# wiring_bord.net
KiCad netlist of a schematic drawn in EAGLE
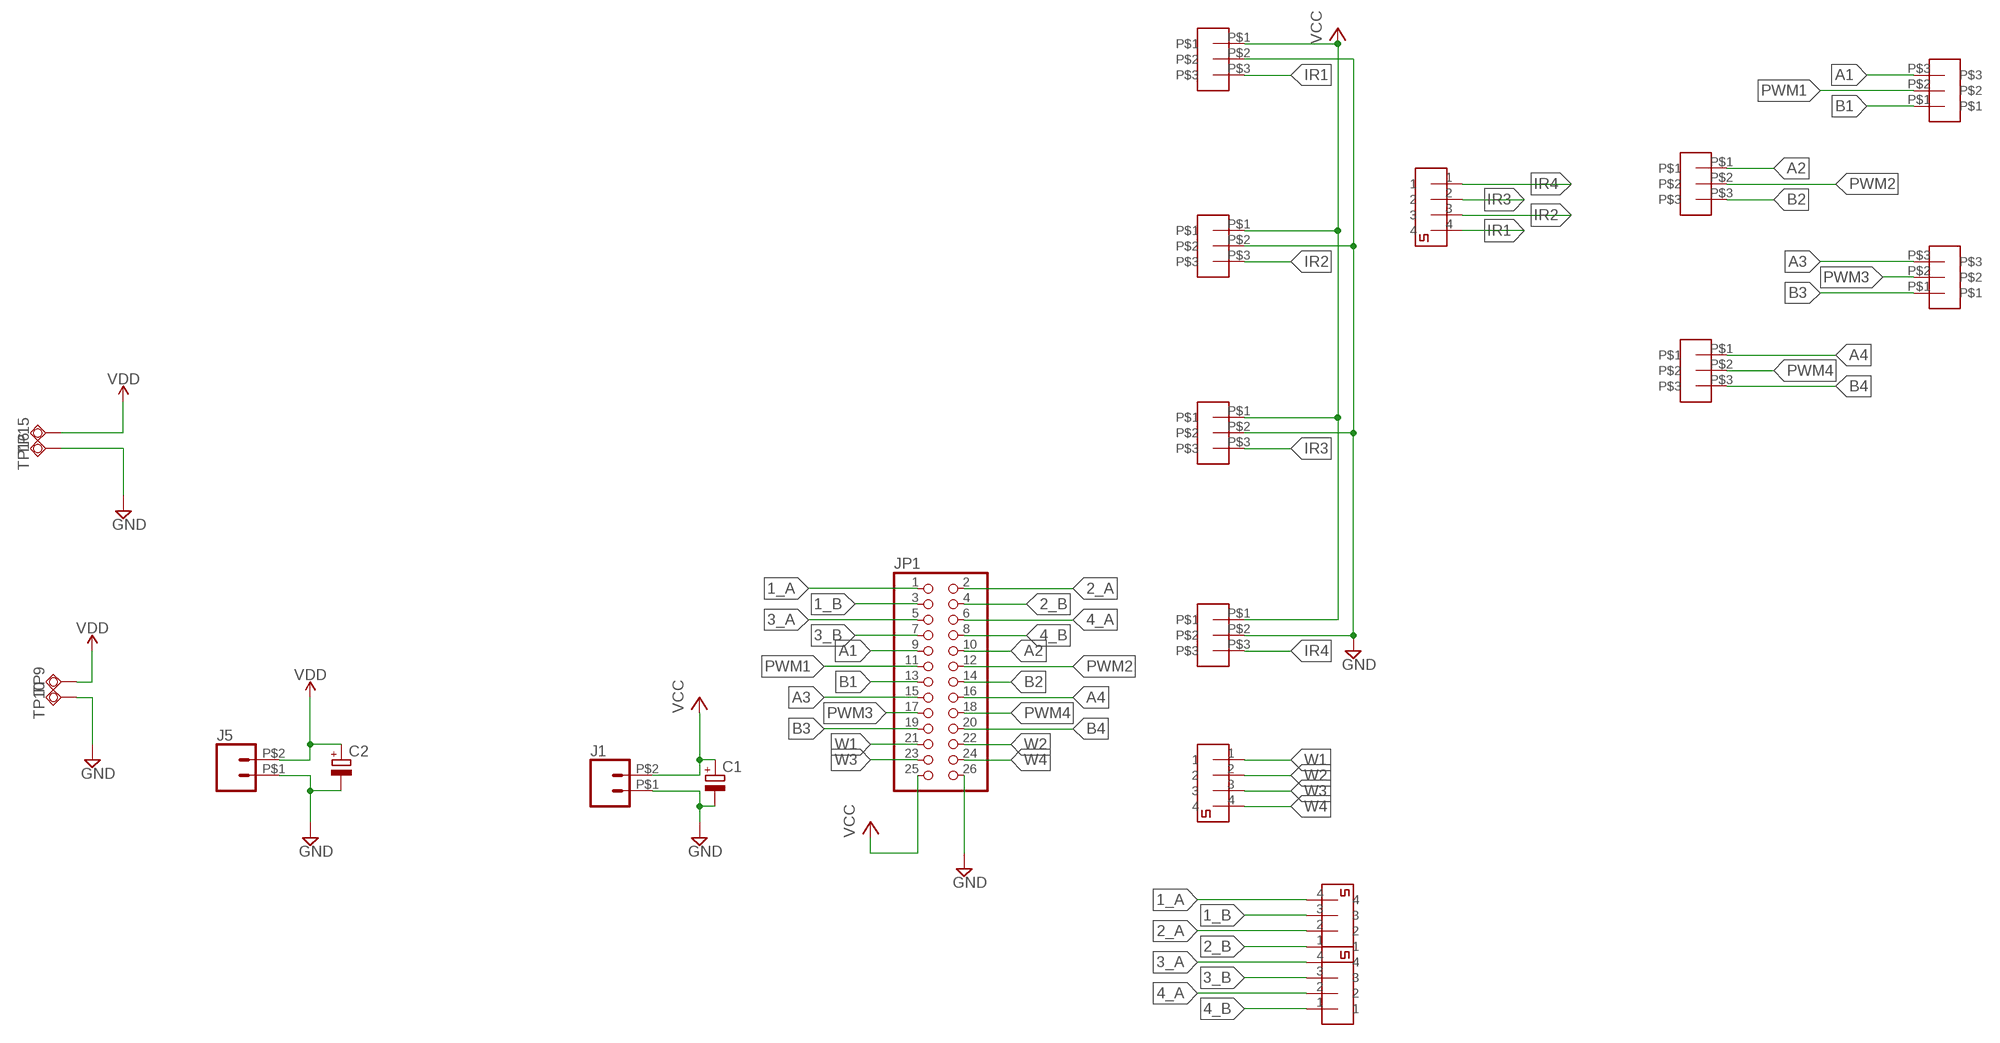
[diagram p0: schematic, sheet 1]

(export (version "E")
  (design (tool "Eeschema 10.0.6"))
  (components
    (comp (ref "C1")
      (value "CPOL-EUE2-5")
      (footprint "eagle-import:E2-5")
      (libsource (lib "eagle-import") (part "CPOL-EUE2-5"))
    )
    (comp (ref "C2")
      (value "CPOL-EUE2-5")
      (footprint "eagle-import:E2-5")
      (libsource (lib "eagle-import") (part "CPOL-EUE2-5"))
    )
    (comp (ref "CONNECTOR1")
      (value "2PIN")
      (footprint "eagle-import:2PIN")
      (libsource (lib "eagle-import") (part "2PIN"))
    )
    (comp (ref "CONNECTOR2")
      (value "2PIN")
      (footprint "eagle-import:2PIN")
      (libsource (lib "eagle-import") (part "2PIN"))
    )
    (comp (ref "CONNECTOR3")
      (value "2PIN")
      (footprint "eagle-import:2PIN")
      (libsource (lib "eagle-import") (part "2PIN"))
    )
    (comp (ref "CONNECTOR4")
      (value "2PIN")
      (footprint "eagle-import:2PIN")
      (libsource (lib "eagle-import") (part "2PIN"))
    )
    (comp (ref "IR_DISTANCE1")
      (value "3PIN")
      (footprint "eagle-import:3PIN")
      (libsource (lib "eagle-import") (part "3PIN"))
    )
    (comp (ref "IR_DISTANCE2")
      (value "3PIN")
      (footprint "eagle-import:3PIN")
      (libsource (lib "eagle-import") (part "3PIN"))
    )
    (comp (ref "IR_DISTANCE3")
      (value "3PIN")
      (footprint "eagle-import:3PIN")
      (libsource (lib "eagle-import") (part "3PIN"))
    )
    (comp (ref "IR_DISTANCE4")
      (value "3PIN")
      (footprint "eagle-import:3PIN")
      (libsource (lib "eagle-import") (part "3PIN"))
    )
    (comp (ref "IR_DISTANCE5")
      (value "3PIN")
      (footprint "eagle-import:3PIN")
      (libsource (lib "eagle-import") (part "3PIN"))
    )
    (comp (ref "IR_DISTANCE6")
      (value "3PIN")
      (footprint "eagle-import:3PIN")
      (libsource (lib "eagle-import") (part "3PIN"))
    )
    (comp (ref "IR_DISTANCE7")
      (value "3PIN")
      (footprint "eagle-import:3PIN")
      (libsource (lib "eagle-import") (part "3PIN"))
    )
    (comp (ref "IR_DISTANCE8")
      (value "3PIN")
      (footprint "eagle-import:3PIN")
      (libsource (lib "eagle-import") (part "3PIN"))
    )
    (comp (ref "J1")
      (value "CONN_02PTH2")
      (footprint "eagle-import:1X02_BIG")
      (libsource (lib "eagle-import") (part "CONN_02PTH2"))
    )
    (comp (ref "J5")
      (value "CONN_02PTH2")
      (footprint "eagle-import:1X02_BIG")
      (libsource (lib "eagle-import") (part "CONN_02PTH2"))
    )
    (comp (ref "JP1")
      (value "PINHD-2X13")
      (footprint "eagle-import:2X13")
      (libsource (lib "eagle-import") (part "PINHD-2X13"))
    )
    (comp (ref "TP9")
      (value "TESTPAD_TPSQPAD1-20")
      (footprint "eagle-import:TESTPAD_P1-20")
      (libsource (lib "eagle-import") (part "TESTPAD_TPSQPAD1-20"))
    )
    (comp (ref "TP10")
      (value "TESTPAD_TPSQPAD1-20")
      (footprint "eagle-import:TESTPAD_P1-20")
      (libsource (lib "eagle-import") (part "TESTPAD_TPSQPAD1-20"))
    )
    (comp (ref "TP15")
      (value "TESTPAD_TPSQPAD1-13")
      (footprint "eagle-import:TESTPAD_P1-13")
      (libsource (lib "eagle-import") (part "TESTPAD_TPSQPAD1-13"))
    )
    (comp (ref "TP16")
      (value "TESTPAD_TPSQPAD1-13")
      (footprint "eagle-import:TESTPAD_P1-13")
      (libsource (lib "eagle-import") (part "TESTPAD_TPSQPAD1-13"))
    )
  )
  (nets
    (net (code "1") (name "1_A") (class "Default")
      (node (ref "CONNECTOR3") (pin "4") (pinfunction "4_4") (pintype "bidirectional"))
      (node (ref "JP1") (pin "1") (pinfunction "1_1") (pintype "passive"))
    )
    (net (code "2") (name "1_B") (class "Default")
      (node (ref "CONNECTOR3") (pin "3") (pinfunction "3_3") (pintype "bidirectional"))
      (node (ref "JP1") (pin "3") (pinfunction "3_3") (pintype "passive"))
    )
    (net (code "3") (name "2_A") (class "Default")
      (node (ref "CONNECTOR3") (pin "2") (pinfunction "2_2") (pintype "bidirectional"))
      (node (ref "JP1") (pin "2") (pinfunction "2_2") (pintype "passive"))
    )
    (net (code "4") (name "2_B") (class "Default")
      (node (ref "CONNECTOR3") (pin "1") (pinfunction "1_1") (pintype "bidirectional"))
      (node (ref "JP1") (pin "4") (pinfunction "4_4") (pintype "passive"))
    )
    (net (code "5") (name "3_A") (class "Default")
      (node (ref "CONNECTOR4") (pin "4") (pinfunction "4_4") (pintype "bidirectional"))
      (node (ref "JP1") (pin "5") (pinfunction "5_5") (pintype "passive"))
    )
    (net (code "6") (name "3_B") (class "Default")
      (node (ref "CONNECTOR4") (pin "3") (pinfunction "3_3") (pintype "bidirectional"))
      (node (ref "JP1") (pin "7") (pinfunction "7_7") (pintype "passive"))
    )
    (net (code "7") (name "4_A") (class "Default")
      (node (ref "CONNECTOR4") (pin "2") (pinfunction "2_2") (pintype "bidirectional"))
      (node (ref "JP1") (pin "6") (pinfunction "6_6") (pintype "passive"))
    )
    (net (code "8") (name "4_B") (class "Default")
      (node (ref "CONNECTOR4") (pin "1") (pinfunction "1_1") (pintype "bidirectional"))
      (node (ref "JP1") (pin "8") (pinfunction "8_8") (pintype "passive"))
    )
    (net (code "9") (name "A1") (class "Default")
      (node (ref "IR_DISTANCE5") (pin "P$3") (pinfunction "P$3_P$3") (pintype "bidirectional"))
      (node (ref "JP1") (pin "9") (pinfunction "9_9") (pintype "passive"))
    )
    (net (code "10") (name "A2") (class "Default")
      (node (ref "IR_DISTANCE6") (pin "P$1") (pinfunction "P$1_P$1") (pintype "bidirectional"))
      (node (ref "JP1") (pin "10") (pinfunction "10_10") (pintype "passive"))
    )
    (net (code "11") (name "A3") (class "Default")
      (node (ref "IR_DISTANCE7") (pin "P$3") (pinfunction "P$3_P$3") (pintype "bidirectional"))
      (node (ref "JP1") (pin "15") (pinfunction "15_15") (pintype "passive"))
    )
    (net (code "12") (name "A4") (class "Default")
      (node (ref "IR_DISTANCE8") (pin "P$1") (pinfunction "P$1_P$1") (pintype "bidirectional"))
      (node (ref "JP1") (pin "16") (pinfunction "16_16") (pintype "passive"))
    )
    (net (code "13") (name "B1") (class "Default")
      (node (ref "IR_DISTANCE5") (pin "P$1") (pinfunction "P$1_P$1") (pintype "bidirectional"))
      (node (ref "JP1") (pin "13") (pinfunction "13_13") (pintype "passive"))
    )
    (net (code "14") (name "B2") (class "Default")
      (node (ref "IR_DISTANCE6") (pin "P$3") (pinfunction "P$3_P$3") (pintype "bidirectional"))
      (node (ref "JP1") (pin "14") (pinfunction "14_14") (pintype "passive"))
    )
    (net (code "15") (name "B3") (class "Default")
      (node (ref "IR_DISTANCE7") (pin "P$1") (pinfunction "P$1_P$1") (pintype "bidirectional"))
      (node (ref "JP1") (pin "19") (pinfunction "19_19") (pintype "passive"))
    )
    (net (code "16") (name "B4") (class "Default")
      (node (ref "IR_DISTANCE8") (pin "P$3") (pinfunction "P$3_P$3") (pintype "bidirectional"))
      (node (ref "JP1") (pin "20") (pinfunction "20_20") (pintype "passive"))
    )
    (net (code "17") (name "GND") (class "Default")
      (node (ref "C1") (pin "-") (pinfunction "-_-") (pintype "passive"))
      (node (ref "C2") (pin "-") (pinfunction "-_-") (pintype "passive"))
      (node (ref "IR_DISTANCE1") (pin "P$2") (pinfunction "P$2_P$2") (pintype "bidirectional"))
      (node (ref "IR_DISTANCE2") (pin "P$2") (pinfunction "P$2_P$2") (pintype "bidirectional"))
      (node (ref "IR_DISTANCE3") (pin "P$2") (pinfunction "P$2_P$2") (pintype "bidirectional"))
      (node (ref "IR_DISTANCE4") (pin "P$2") (pinfunction "P$2_P$2") (pintype "bidirectional"))
      (node (ref "J1") (pin "P$1") (pinfunction "1_P$1") (pintype "passive"))
      (node (ref "J5") (pin "P$1") (pinfunction "1_P$1") (pintype "passive"))
      (node (ref "JP1") (pin "26") (pinfunction "26_26") (pintype "passive"))
      (node (ref "TP10") (pin "TP") (pinfunction "TP_TP") (pintype "input"))
      (node (ref "TP16") (pin "TP") (pinfunction "TP_TP") (pintype "input"))
    )
    (net (code "18") (name "IR1") (class "Default")
      (node (ref "CONNECTOR1") (pin "4") (pinfunction "4_4") (pintype "bidirectional"))
      (node (ref "IR_DISTANCE1") (pin "P$3") (pinfunction "P$3_P$3") (pintype "bidirectional"))
    )
    (net (code "19") (name "IR2") (class "Default")
      (node (ref "CONNECTOR1") (pin "3") (pinfunction "3_3") (pintype "bidirectional"))
      (node (ref "IR_DISTANCE2") (pin "P$3") (pinfunction "P$3_P$3") (pintype "bidirectional"))
    )
    (net (code "20") (name "IR3") (class "Default")
      (node (ref "CONNECTOR1") (pin "2") (pinfunction "2_2") (pintype "bidirectional"))
      (node (ref "IR_DISTANCE3") (pin "P$3") (pinfunction "P$3_P$3") (pintype "bidirectional"))
    )
    (net (code "21") (name "IR4") (class "Default")
      (node (ref "CONNECTOR1") (pin "1") (pinfunction "1_1") (pintype "bidirectional"))
      (node (ref "IR_DISTANCE4") (pin "P$3") (pinfunction "P$3_P$3") (pintype "bidirectional"))
    )
    (net (code "22") (name "PWM1") (class "Default")
      (node (ref "IR_DISTANCE5") (pin "P$2") (pinfunction "P$2_P$2") (pintype "bidirectional"))
      (node (ref "JP1") (pin "11") (pinfunction "11_11") (pintype "passive"))
    )
    (net (code "23") (name "PWM2") (class "Default")
      (node (ref "IR_DISTANCE6") (pin "P$2") (pinfunction "P$2_P$2") (pintype "bidirectional"))
      (node (ref "JP1") (pin "12") (pinfunction "12_12") (pintype "passive"))
    )
    (net (code "24") (name "PWM3") (class "Default")
      (node (ref "IR_DISTANCE7") (pin "P$2") (pinfunction "P$2_P$2") (pintype "bidirectional"))
      (node (ref "JP1") (pin "17") (pinfunction "17_17") (pintype "passive"))
    )
    (net (code "25") (name "PWM4") (class "Default")
      (node (ref "IR_DISTANCE8") (pin "P$2") (pinfunction "P$2_P$2") (pintype "bidirectional"))
      (node (ref "JP1") (pin "18") (pinfunction "18_18") (pintype "passive"))
    )
    (net (code "26") (name "VCC") (class "Default")
      (node (ref "C1") (pin "+") (pinfunction "+_+") (pintype "passive"))
      (node (ref "IR_DISTANCE1") (pin "P$1") (pinfunction "P$1_P$1") (pintype "bidirectional"))
      (node (ref "IR_DISTANCE2") (pin "P$1") (pinfunction "P$1_P$1") (pintype "bidirectional"))
      (node (ref "IR_DISTANCE3") (pin "P$1") (pinfunction "P$1_P$1") (pintype "bidirectional"))
      (node (ref "IR_DISTANCE4") (pin "P$1") (pinfunction "P$1_P$1") (pintype "bidirectional"))
      (node (ref "J1") (pin "P$2") (pinfunction "2_P$2") (pintype "passive"))
      (node (ref "JP1") (pin "25") (pinfunction "25_25") (pintype "passive"))
    )
    (net (code "27") (name "VDD") (class "Default")
      (node (ref "C2") (pin "+") (pinfunction "+_+") (pintype "passive"))
      (node (ref "J5") (pin "P$2") (pinfunction "2_P$2") (pintype "passive"))
      (node (ref "TP15") (pin "TP") (pinfunction "TP_TP") (pintype "input"))
      (node (ref "TP9") (pin "TP") (pinfunction "TP_TP") (pintype "input"))
    )
    (net (code "28") (name "W1") (class "Default")
      (node (ref "CONNECTOR2") (pin "1") (pinfunction "1_1") (pintype "bidirectional"))
      (node (ref "JP1") (pin "21") (pinfunction "21_21") (pintype "passive"))
    )
    (net (code "29") (name "W2") (class "Default")
      (node (ref "CONNECTOR2") (pin "2") (pinfunction "2_2") (pintype "bidirectional"))
      (node (ref "JP1") (pin "22") (pinfunction "22_22") (pintype "passive"))
    )
    (net (code "30") (name "W3") (class "Default")
      (node (ref "CONNECTOR2") (pin "3") (pinfunction "3_3") (pintype "bidirectional"))
      (node (ref "JP1") (pin "23") (pinfunction "23_23") (pintype "passive"))
    )
    (net (code "31") (name "W4") (class "Default")
      (node (ref "CONNECTOR2") (pin "4") (pinfunction "4_4") (pintype "bidirectional"))
      (node (ref "JP1") (pin "24") (pinfunction "24_24") (pintype "passive"))
    )
  )
)
